# LED_board.net
KiCad netlist of a schematic drawn in EAGLE
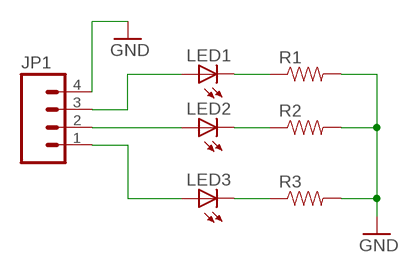
[diagram p0: schematic, sheet 1]

(export (version "E")
  (design (tool "Eeschema 10.0.6"))
  (components
    (comp (ref "JP1")
      (value "M04LOCK")
      (footprint "eagle-import:1X04_LOCK")
      (libsource (lib "eagle-import") (part "M04LOCK"))
    )
    (comp (ref "LED1")
      (value "LED3MM")
      (footprint "eagle-import:LED3MM")
      (libsource (lib "eagle-import") (part "LED3MM"))
    )
    (comp (ref "LED2")
      (value "LED3MM")
      (footprint "eagle-import:LED3MM")
      (libsource (lib "eagle-import") (part "LED3MM"))
    )
    (comp (ref "LED3")
      (value "LED3MM")
      (footprint "eagle-import:LED3MM")
      (libsource (lib "eagle-import") (part "LED3MM"))
    )
    (comp (ref "R1")
      (value "RESISTORPTH-1/6W")
      (footprint "eagle-import:1_6W-RES")
      (libsource (lib "eagle-import") (part "RESISTORPTH-1/6W"))
    )
    (comp (ref "R2")
      (value "RESISTORPTH-1/6W")
      (footprint "eagle-import:1_6W-RES")
      (libsource (lib "eagle-import") (part "RESISTORPTH-1/6W"))
    )
    (comp (ref "R3")
      (value "RESISTORPTH-1/6W")
      (footprint "eagle-import:1_6W-RES")
      (libsource (lib "eagle-import") (part "RESISTORPTH-1/6W"))
    )
  )
  (nets
    (net (code "1") (name "GND") (class "Default")
      (node (ref "JP1") (pin "4") (pinfunction "4_4") (pintype "passive"))
      (node (ref "R1") (pin "2") (pinfunction "2_2") (pintype "passive"))
      (node (ref "R2") (pin "2") (pinfunction "2_2") (pintype "passive"))
      (node (ref "R3") (pin "2") (pinfunction "2_2") (pintype "passive"))
    )
    (net (code "2") (name "Net-(JP1-Pad1)") (class "Default")
      (node (ref "JP1") (pin "1") (pinfunction "1_1") (pintype "passive"))
      (node (ref "LED3") (pin "A") (pinfunction "A_A") (pintype "passive"))
    )
    (net (code "3") (name "Net-(JP1-Pad2)") (class "Default")
      (node (ref "JP1") (pin "2") (pinfunction "2_2") (pintype "passive"))
      (node (ref "LED2") (pin "A") (pinfunction "A_A") (pintype "passive"))
    )
    (net (code "4") (name "Net-(JP1-Pad3)") (class "Default")
      (node (ref "JP1") (pin "3") (pinfunction "3_3") (pintype "passive"))
      (node (ref "LED1") (pin "A") (pinfunction "A_A") (pintype "passive"))
    )
    (net (code "5") (name "Net-(LED1-C)") (class "Default")
      (node (ref "LED1") (pin "K") (pinfunction "C_K") (pintype "passive"))
      (node (ref "R1") (pin "1") (pinfunction "1_1") (pintype "passive"))
    )
    (net (code "6") (name "Net-(LED2-C)") (class "Default")
      (node (ref "LED2") (pin "K") (pinfunction "C_K") (pintype "passive"))
      (node (ref "R2") (pin "1") (pinfunction "1_1") (pintype "passive"))
    )
    (net (code "7") (name "Net-(LED3-C)") (class "Default")
      (node (ref "LED3") (pin "K") (pinfunction "C_K") (pintype "passive"))
      (node (ref "R3") (pin "1") (pinfunction "1_1") (pintype "passive"))
    )
  )
)
